# myPCB2.net
KiCad netlist of a schematic drawn in EAGLE
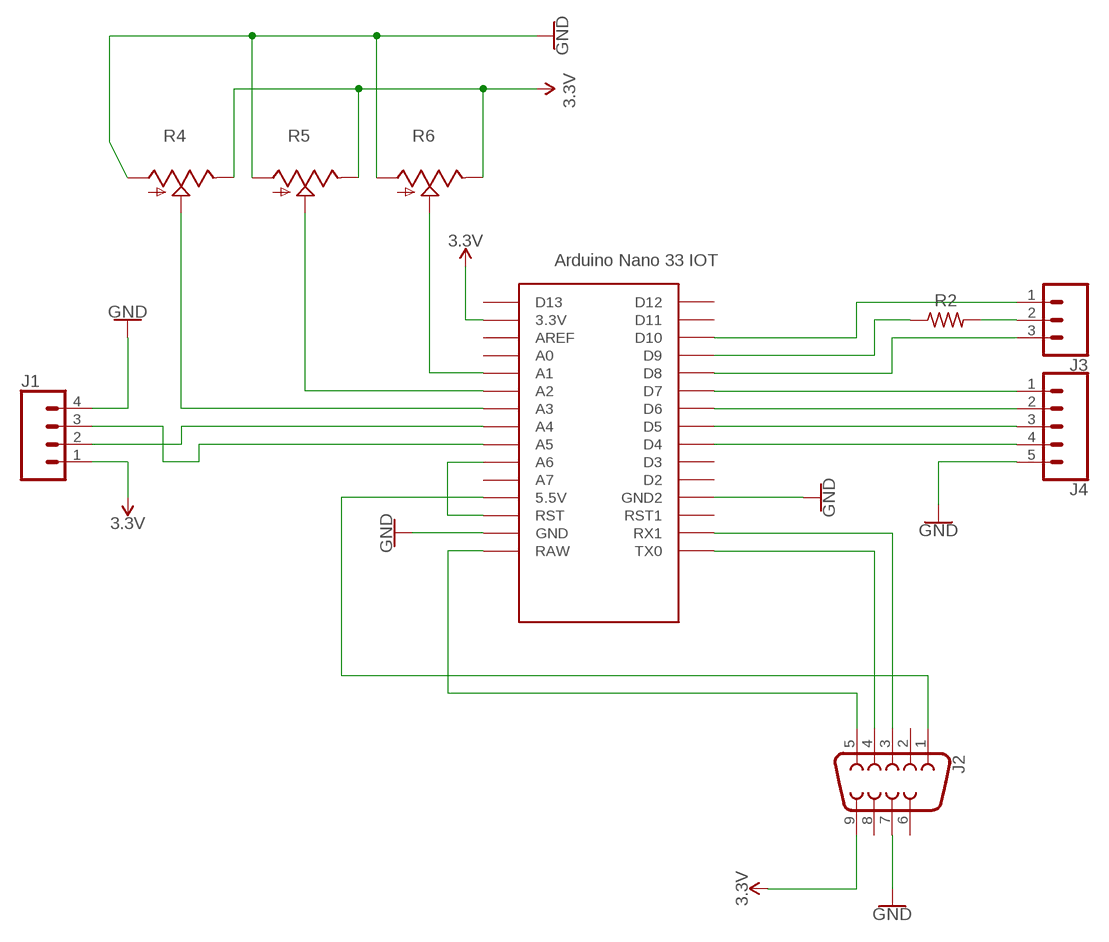
[diagram p0: schematic, sheet 1]

(export (version "E")
  (design (tool "Eeschema 10.0.6"))
  (components
    (comp (ref "J1")
      (value "CONN_04")
      (footprint "eagle-import:1X04")
      (libsource (lib "eagle-import") (part "CONN_04"))
    )
    (comp (ref "J2")
      (value "DB9FEMALE")
      (footprint "eagle-import:DB9")
      (libsource (lib "eagle-import") (part "DB9FEMALE"))
    )
    (comp (ref "J3")
      (value "CONN_03")
      (footprint "eagle-import:1X03")
      (libsource (lib "eagle-import") (part "CONN_03"))
    )
    (comp (ref "J4")
      (value "CONN_05")
      (footprint "eagle-import:1X05")
      (libsource (lib "eagle-import") (part "CONN_05"))
    )
    (comp (ref "R2")
      (value "R-US_AXIAL-7.2MM-PITCH")
      (footprint "eagle-import:RESAD724W46L381D178B")
      (libsource (lib "eagle-import") (part "R-USAXIAL-7.2MM-PITCH_"))
    )
    (comp (ref "R4")
      (value "TRIM_US-S63P")
      (footprint "eagle-import:S63P")
      (libsource (lib "eagle-import") (part "TRIM_US-S63P"))
    )
    (comp (ref "R5")
      (value "TRIM_US-S63P")
      (footprint "eagle-import:S63P")
      (libsource (lib "eagle-import") (part "TRIM_US-S63P"))
    )
    (comp (ref "R6")
      (value "TRIM_US-S63P")
      (footprint "eagle-import:S63P")
      (libsource (lib "eagle-import") (part "TRIM_US-S63P"))
    )
    (comp (ref "U$2")
      (value "NANO33IOT")
      (footprint "eagle-import:NANO33IOT")
      (libsource (lib "eagle-import") (part "NANO33IOT"))
    )
  )
  (nets
    (net (code "1") (name "3.3V") (class "Default")
      (node (ref "J1") (pin "1") (pinfunction "1_1") (pintype "passive"))
      (node (ref "J2") (pin "9") (pinfunction "9_9") (pintype "passive"))
      (node (ref "R4") (pin "E") (pinfunction "E_E") (pintype "passive"))
      (node (ref "R5") (pin "E") (pinfunction "E_E") (pintype "passive"))
      (node (ref "R6") (pin "E") (pinfunction "E_E") (pintype "passive"))
      (node (ref "U$2") (pin "3.3V") (pinfunction "3.3V_3.3V") (pintype "bidirectional"))
    )
    (net (code "2") (name "GND") (class "Default")
      (node (ref "J1") (pin "4") (pinfunction "4_4") (pintype "passive"))
      (node (ref "J2") (pin "7") (pinfunction "7_7") (pintype "passive"))
      (node (ref "J4") (pin "5") (pinfunction "5_5") (pintype "passive"))
      (node (ref "R4") (pin "A") (pinfunction "A_A") (pintype "passive"))
      (node (ref "R5") (pin "A") (pinfunction "A_A") (pintype "passive"))
      (node (ref "R6") (pin "A") (pinfunction "A_A") (pintype "passive"))
      (node (ref "U$2") (pin "GND") (pinfunction "GND_GND") (pintype "bidirectional"))
      (node (ref "U$2") (pin "GND1") (pinfunction "GND2_GND1") (pintype "bidirectional"))
    )
    (net (code "3") (name "Net-(J1-Pad2)") (class "Default")
      (node (ref "J1") (pin "2") (pinfunction "2_2") (pintype "passive"))
      (node (ref "U$2") (pin "A4") (pinfunction "A4_A4") (pintype "bidirectional"))
    )
    (net (code "4") (name "Net-(J1-Pad3)") (class "Default")
      (node (ref "J1") (pin "3") (pinfunction "3_3") (pintype "passive"))
      (node (ref "U$2") (pin "A5") (pinfunction "A5_A5") (pintype "bidirectional"))
    )
    (net (code "5") (name "Net-(J2-Pad3)") (class "Default")
      (node (ref "J2") (pin "3") (pinfunction "3_3") (pintype "passive"))
      (node (ref "U$2") (pin "RX1") (pinfunction "RX1_RX1") (pintype "bidirectional"))
    )
    (net (code "6") (name "Net-(J2-Pad4)") (class "Default")
      (node (ref "J2") (pin "4") (pinfunction "4_4") (pintype "passive"))
      (node (ref "U$2") (pin "TX0") (pinfunction "TX0_TX0") (pintype "bidirectional"))
    )
    (net (code "7") (name "Net-(J2-Pad5)") (class "Default")
      (node (ref "J2") (pin "5") (pinfunction "5_5") (pintype "passive"))
      (node (ref "U$2") (pin "RAW") (pinfunction "RAW_RAW") (pintype "bidirectional"))
    )
    (net (code "8") (name "Net-(J3-Pad1)") (class "Default")
      (node (ref "J3") (pin "1") (pinfunction "1_1") (pintype "passive"))
      (node (ref "U$2") (pin "D10") (pinfunction "D10_D10") (pintype "bidirectional"))
    )
    (net (code "9") (name "Net-(J3-Pad2)") (class "Default")
      (node (ref "J3") (pin "2") (pinfunction "2_2") (pintype "passive"))
      (node (ref "R2") (pin "2") (pinfunction "2_2") (pintype "passive"))
    )
    (net (code "10") (name "Net-(J3-Pad3)") (class "Default")
      (node (ref "J3") (pin "3") (pinfunction "3_3") (pintype "passive"))
      (node (ref "U$2") (pin "D8") (pinfunction "D8_D8") (pintype "bidirectional"))
    )
    (net (code "11") (name "Net-(J4-Pad1)") (class "Default")
      (node (ref "J4") (pin "1") (pinfunction "1_1") (pintype "passive"))
      (node (ref "U$2") (pin "D7") (pinfunction "D7_D7") (pintype "bidirectional"))
    )
    (net (code "12") (name "Net-(J4-Pad2)") (class "Default")
      (node (ref "J4") (pin "2") (pinfunction "2_2") (pintype "passive"))
      (node (ref "U$2") (pin "D6") (pinfunction "D6_D6") (pintype "bidirectional"))
    )
    (net (code "13") (name "Net-(J4-Pad3)") (class "Default")
      (node (ref "J4") (pin "3") (pinfunction "3_3") (pintype "passive"))
      (node (ref "U$2") (pin "D5") (pinfunction "D5_D5") (pintype "bidirectional"))
    )
    (net (code "14") (name "Net-(J4-Pad4)") (class "Default")
      (node (ref "J4") (pin "4") (pinfunction "4_4") (pintype "passive"))
      (node (ref "U$2") (pin "D4") (pinfunction "D4_D4") (pintype "bidirectional"))
    )
    (net (code "15") (name "Net-(R2-Pad1)") (class "Default")
      (node (ref "R2") (pin "1") (pinfunction "1_1") (pintype "passive"))
      (node (ref "U$2") (pin "D9") (pinfunction "D9_D9") (pintype "bidirectional"))
    )
    (net (code "16") (name "Net-(R4-PadS)") (class "Default")
      (node (ref "R4") (pin "S") (pinfunction "S_S") (pintype "passive"))
      (node (ref "U$2") (pin "A3") (pinfunction "A3_A3") (pintype "bidirectional"))
    )
    (net (code "17") (name "Net-(R5-PadS)") (class "Default")
      (node (ref "R5") (pin "S") (pinfunction "S_S") (pintype "passive"))
      (node (ref "U$2") (pin "A2") (pinfunction "A2_A2") (pintype "bidirectional"))
    )
    (net (code "18") (name "Net-(R6-PadS)") (class "Default")
      (node (ref "R6") (pin "S") (pinfunction "S_S") (pintype "passive"))
      (node (ref "U$2") (pin "A1") (pinfunction "A1_A1") (pintype "bidirectional"))
    )
    (net (code "19") (name "Net-(U$2-5.5V)") (class "Default")
      (node (ref "J2") (pin "1") (pinfunction "1_1") (pintype "passive"))
      (node (ref "U$2") (pin "5V") (pinfunction "5.5V_5V") (pintype "bidirectional"))
    )
    (net (code "20") (name "Net-(U$2-PadA6)") (class "Default")
      (node (ref "U$2") (pin "A6") (pinfunction "A6_A6") (pintype "bidirectional"))
      (node (ref "U$2") (pin "RST") (pinfunction "RST_RST") (pintype "bidirectional"))
    )
    (net (code "21") (name "unconnected-(J2-Pad2)") (class "Default")
      (node (ref "J2") (pin "2") (pinfunction "2_2") (pintype "passive"))
    )
    (net (code "22") (name "unconnected-(J2-Pad6)") (class "Default")
      (node (ref "J2") (pin "6") (pinfunction "6_6") (pintype "passive"))
    )
    (net (code "23") (name "unconnected-(J2-Pad8)") (class "Default")
      (node (ref "J2") (pin "8") (pinfunction "8_8") (pintype "passive"))
    )
    (net (code "24") (name "unconnected-(U$2-PadA0)") (class "Default")
      (node (ref "U$2") (pin "A0") (pinfunction "A0_A0") (pintype "bidirectional"))
    )
    (net (code "25") (name "unconnected-(U$2-PadA7)") (class "Default")
      (node (ref "U$2") (pin "A7") (pinfunction "A7_A7") (pintype "bidirectional"))
    )
    (net (code "26") (name "unconnected-(U$2-PadAREF)") (class "Default")
      (node (ref "U$2") (pin "AREF") (pinfunction "AREF_AREF") (pintype "bidirectional"))
    )
    (net (code "27") (name "unconnected-(U$2-PadD2)") (class "Default")
      (node (ref "U$2") (pin "D2") (pinfunction "D2_D2") (pintype "bidirectional"))
    )
    (net (code "28") (name "unconnected-(U$2-PadD3)") (class "Default")
      (node (ref "U$2") (pin "D3") (pinfunction "D3_D3") (pintype "bidirectional"))
    )
    (net (code "29") (name "unconnected-(U$2-PadD11)") (class "Default")
      (node (ref "U$2") (pin "D11") (pinfunction "D11_D11") (pintype "bidirectional"))
    )
    (net (code "30") (name "unconnected-(U$2-PadD12)") (class "Default")
      (node (ref "U$2") (pin "D12") (pinfunction "D12_D12") (pintype "bidirectional"))
    )
    (net (code "31") (name "unconnected-(U$2-PadD13)") (class "Default")
      (node (ref "U$2") (pin "D13") (pinfunction "D13_D13") (pintype "bidirectional"))
    )
    (net (code "32") (name "unconnected-(U$2-PadRST1)") (class "Default")
      (node (ref "U$2") (pin "RST1") (pinfunction "RST1_RST1") (pintype "bidirectional"))
    )
  )
)
